# progtypec2.net
KiCad netlist of a schematic drawn in EAGLE
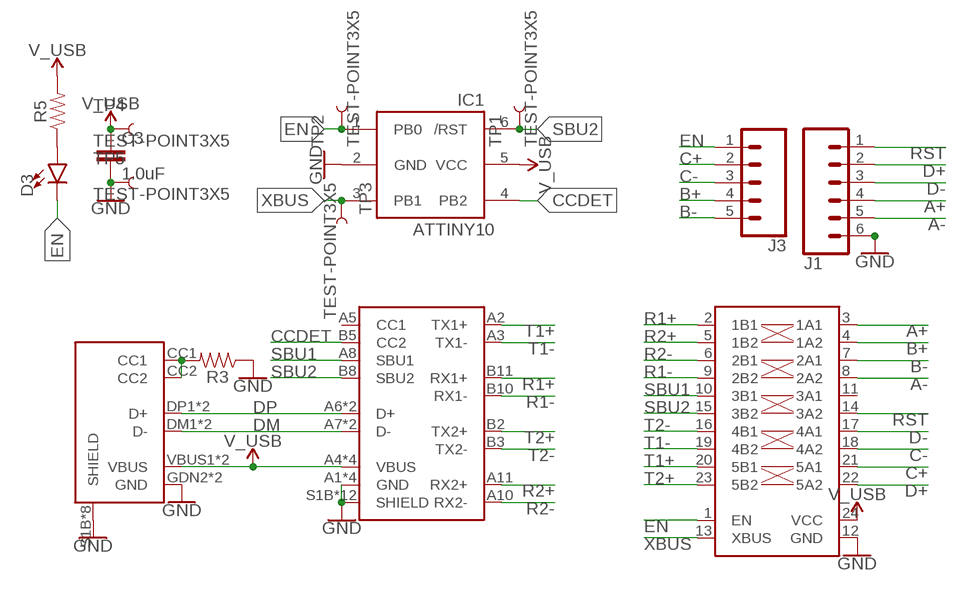
[diagram p0: schematic, sheet 1]

(export (version "E")
  (design (tool "Eeschema 10.0.6"))
  (components
    (comp (ref "C3")
      (value "1.0uF")
      (footprint "eagle-import:0603")
      (libsource (lib "eagle-import") (part "1.0UF-0603-16V-10%"))
    )
    (comp (ref "D3")
      (value "LED0603")
      (footprint "eagle-import:LED-0603")
      (libsource (lib "eagle-import") (part "LED0603"))
    )
    (comp (ref "IC1")
      (value "ATTINY10")
      (footprint "eagle-import:SOT23-6")
      (libsource (lib "eagle-import") (part "ATTINY10"))
    )
    (comp (ref "J1")
      (value "CONN_06NO_SILK_FEMALE_PTH")
      (footprint "eagle-import:1X06_NO_SILK")
      (libsource (lib "eagle-import") (part "CONN_06NO_SILK_FEMALE_PTH"))
    )
    (comp (ref "J3")
      (value "CONN_05NO_SILK")
      (footprint "eagle-import:1X05_NO_SILK")
      (libsource (lib "eagle-import") (part "CONN_05NO_SILK"))
    )
    (comp (ref "R3")
      (value "RESISTOR0603")
      (footprint "eagle-import:0603")
      (libsource (lib "eagle-import") (part "RESISTOR0603"))
    )
    (comp (ref "R5")
      (value "RESISTOR0603")
      (footprint "eagle-import:0603")
      (libsource (lib "eagle-import") (part "RESISTOR0603"))
    )
    (comp (ref "TP1")
      (value "TEST-POINT3X5")
      (footprint "eagle-import:PAD.03X.05")
      (libsource (lib "eagle-import") (part "TEST-POINT3X5"))
    )
    (comp (ref "TP2")
      (value "TEST-POINT3X5")
      (footprint "eagle-import:PAD.03X.05")
      (libsource (lib "eagle-import") (part "TEST-POINT3X5"))
    )
    (comp (ref "TP3")
      (value "TEST-POINT3X5")
      (footprint "eagle-import:PAD.03X.05")
      (libsource (lib "eagle-import") (part "TEST-POINT3X5"))
    )
    (comp (ref "TP4")
      (value "TEST-POINT3X5")
      (footprint "eagle-import:PAD.03X.05")
      (libsource (lib "eagle-import") (part "TEST-POINT3X5"))
    )
    (comp (ref "TP5")
      (value "TEST-POINT3X5")
      (footprint "eagle-import:PAD.03X.05")
      (libsource (lib "eagle-import") (part "TEST-POINT3X5"))
    )
    (comp (ref "U$1")
      (value "USB-C-HORZ-F")
      (footprint "eagle-import:USB-C_24PIN_HORZ-F-UNTESTED")
      (libsource (lib "eagle-import") (part "USB-C-HORZ-F"))
    )
    (comp (ref "U$2")
      (value "USB-C_USB2ONLY-HORZ-F_12P")
      (footprint "eagle-import:USB-C_12PIN_HORZ-F")
      (libsource (lib "eagle-import") (part "USB-C_USB2ONLY-HORZ-F_12P"))
    )
    (comp (ref "U$3")
      (value "SN74CBT3383C")
      (footprint "eagle-import:TSSOP24")
      (libsource (lib "eagle-import") (part "SN74CBT3383C"))
    )
  )
  (nets
    (net (code "1") (name "A+") (class "Default")
      (node (ref "J1") (pin "4") (pinfunction "4_4") (pintype "passive"))
      (node (ref "U$3") (pin "3") (pinfunction "1A1_3") (pintype "bidirectional"))
    )
    (net (code "2") (name "A-") (class "Default")
      (node (ref "J1") (pin "5") (pinfunction "5_5") (pintype "passive"))
      (node (ref "U$3") (pin "8") (pinfunction "2A2_8") (pintype "bidirectional"))
    )
    (net (code "3") (name "B+") (class "Default")
      (node (ref "J3") (pin "4") (pinfunction "4_4") (pintype "passive"))
      (node (ref "U$3") (pin "4") (pinfunction "1A2_4") (pintype "bidirectional"))
    )
    (net (code "4") (name "B-") (class "Default")
      (node (ref "J3") (pin "5") (pinfunction "5_5") (pintype "passive"))
      (node (ref "U$3") (pin "7") (pinfunction "2A1_7") (pintype "bidirectional"))
    )
    (net (code "5") (name "C+") (class "Default")
      (node (ref "J3") (pin "2") (pinfunction "2_2") (pintype "passive"))
      (node (ref "U$3") (pin "21") (pinfunction "5A1_21") (pintype "bidirectional"))
    )
    (net (code "6") (name "C-") (class "Default")
      (node (ref "J3") (pin "3") (pinfunction "3_3") (pintype "passive"))
      (node (ref "U$3") (pin "18") (pinfunction "4A2_18") (pintype "bidirectional"))
    )
    (net (code "7") (name "CCDET") (class "Default")
      (node (ref "IC1") (pin "4") (pinfunction "PB2_4") (pintype "bidirectional"))
      (node (ref "U$1") (pin "B5") (pinfunction "CC2_B5") (pintype "bidirectional"))
    )
    (net (code "8") (name "D+") (class "Default")
      (node (ref "J1") (pin "2") (pinfunction "2_2") (pintype "passive"))
      (node (ref "U$3") (pin "22") (pinfunction "5A2_22") (pintype "bidirectional"))
    )
    (net (code "9") (name "D-") (class "Default")
      (node (ref "J1") (pin "3") (pinfunction "3_3") (pintype "passive"))
      (node (ref "U$3") (pin "17") (pinfunction "4A1_17") (pintype "bidirectional"))
    )
    (net (code "10") (name "DM") (class "Default")
      (node (ref "U$1") (pin "A7") (pinfunction "D-_A7") (pintype "bidirectional"))
      (node (ref "U$1") (pin "B7") (pinfunction "D-_B7") (pintype "bidirectional"))
      (node (ref "U$2") (pin "DM1") (pinfunction "D-_DM1") (pintype "bidirectional"))
      (node (ref "U$2") (pin "DM2") (pinfunction "D-_DM2") (pintype "bidirectional"))
    )
    (net (code "11") (name "DP") (class "Default")
      (node (ref "U$1") (pin "A6") (pinfunction "D+_A6") (pintype "bidirectional"))
      (node (ref "U$1") (pin "B6") (pinfunction "D+_B6") (pintype "bidirectional"))
      (node (ref "U$2") (pin "DP1") (pinfunction "D+_DP1") (pintype "bidirectional"))
      (node (ref "U$2") (pin "DP2") (pinfunction "D+_DP2") (pintype "bidirectional"))
    )
    (net (code "12") (name "EN") (class "Default")
      (node (ref "D3") (pin "C") (pinfunction "C_C") (pintype "passive"))
      (node (ref "IC1") (pin "1") (pinfunction "PB0_1") (pintype "bidirectional"))
      (node (ref "J3") (pin "1") (pinfunction "1_1") (pintype "passive"))
      (node (ref "TP2") (pin "P$1") (pinfunction "1_P$1") (pintype "bidirectional"))
      (node (ref "U$3") (pin "1") (pinfunction "EN_1") (pintype "bidirectional"))
    )
    (net (code "13") (name "GND") (class "Default")
      (node (ref "C3") (pin "2") (pinfunction "2_2") (pintype "passive"))
      (node (ref "IC1") (pin "2") (pinfunction "GND_2") (pintype "power_in"))
      (node (ref "J1") (pin "6") (pinfunction "6_6") (pintype "passive"))
      (node (ref "R3") (pin "1") (pinfunction "1_1") (pintype "passive"))
      (node (ref "TP5") (pin "P$1") (pinfunction "1_P$1") (pintype "bidirectional"))
      (node (ref "U$1") (pin "A1") (pinfunction "GND_A1") (pintype "bidirectional"))
      (node (ref "U$1") (pin "A12") (pinfunction "GND_A12") (pintype "bidirectional"))
      (node (ref "U$1") (pin "B1") (pinfunction "GND_B1") (pintype "bidirectional"))
      (node (ref "U$1") (pin "B12") (pinfunction "GND_B12") (pintype "bidirectional"))
      (node (ref "U$1") (pin "S1B") (pinfunction "SHIELD_S1B") (pintype "bidirectional"))
      (node (ref "U$1") (pin "S1T") (pinfunction "SHIELD_S1T") (pintype "bidirectional"))
      (node (ref "U$1") (pin "S2B") (pinfunction "SHIELD_S2B") (pintype "bidirectional"))
      (node (ref "U$1") (pin "S2T") (pinfunction "SHIELD_S2T") (pintype "bidirectional"))
      (node (ref "U$1") (pin "S3B") (pinfunction "SHIELD_S3B") (pintype "bidirectional"))
      (node (ref "U$1") (pin "S3T") (pinfunction "SHIELD_S3T") (pintype "bidirectional"))
      (node (ref "U$1") (pin "S4B") (pinfunction "SHIELD_S4B") (pintype "bidirectional"))
      (node (ref "U$1") (pin "S4T") (pinfunction "SHIELD_S4T") (pintype "bidirectional"))
      (node (ref "U$1") (pin "S5B") (pinfunction "SHIELD_S5B") (pintype "bidirectional"))
      (node (ref "U$1") (pin "S5T") (pinfunction "SHIELD_S5T") (pintype "bidirectional"))
      (node (ref "U$1") (pin "S6B") (pinfunction "SHIELD_S6B") (pintype "bidirectional"))
      (node (ref "U$1") (pin "S6T") (pinfunction "SHIELD_S6T") (pintype "bidirectional"))
      (node (ref "U$2") (pin "GDN2") (pinfunction "GND_GDN2") (pintype "bidirectional"))
      (node (ref "U$2") (pin "GND1") (pinfunction "GND_GND1") (pintype "bidirectional"))
      (node (ref "U$2") (pin "S1B") (pinfunction "SHIELD_S1B") (pintype "bidirectional"))
      (node (ref "U$2") (pin "S1T") (pinfunction "SHIELD_S1T") (pintype "bidirectional"))
      (node (ref "U$2") (pin "S2B") (pinfunction "SHIELD_S2B") (pintype "bidirectional"))
      (node (ref "U$2") (pin "S2T") (pinfunction "SHIELD_S2T") (pintype "bidirectional"))
      (node (ref "U$2") (pin "S3B") (pinfunction "SHIELD_S3B") (pintype "bidirectional"))
      (node (ref "U$2") (pin "S3T") (pinfunction "SHIELD_S3T") (pintype "bidirectional"))
      (node (ref "U$2") (pin "S4B") (pinfunction "SHIELD_S4B") (pintype "bidirectional"))
      (node (ref "U$2") (pin "S4T") (pinfunction "SHIELD_S4T") (pintype "bidirectional"))
      (node (ref "U$3") (pin "12") (pinfunction "GND_12") (pintype "bidirectional"))
    )
    (net (code "14") (name "Net-(D3-PadA)") (class "Default")
      (node (ref "D3") (pin "A") (pinfunction "A_A") (pintype "passive"))
      (node (ref "R5") (pin "1") (pinfunction "1_1") (pintype "passive"))
    )
    (net (code "15") (name "Net-(R3-Pad2)") (class "Default")
      (node (ref "R3") (pin "2") (pinfunction "2_2") (pintype "passive"))
      (node (ref "U$2") (pin "CC1") (pinfunction "CC1_CC1") (pintype "bidirectional"))
      (node (ref "U$2") (pin "CC2") (pinfunction "CC2_CC2") (pintype "bidirectional"))
    )
    (net (code "16") (name "R1+") (class "Default")
      (node (ref "U$1") (pin "B11") (pinfunction "RX1+_B11") (pintype "bidirectional"))
      (node (ref "U$3") (pin "2") (pinfunction "1B1_2") (pintype "bidirectional"))
    )
    (net (code "17") (name "R1-") (class "Default")
      (node (ref "U$1") (pin "B10") (pinfunction "RX1-_B10") (pintype "bidirectional"))
      (node (ref "U$3") (pin "9") (pinfunction "2B2_9") (pintype "bidirectional"))
    )
    (net (code "18") (name "R2+") (class "Default")
      (node (ref "U$1") (pin "A11") (pinfunction "RX2+_A11") (pintype "bidirectional"))
      (node (ref "U$3") (pin "5") (pinfunction "1B2_5") (pintype "bidirectional"))
    )
    (net (code "19") (name "R2-") (class "Default")
      (node (ref "U$1") (pin "A10") (pinfunction "RX2-_A10") (pintype "bidirectional"))
      (node (ref "U$3") (pin "6") (pinfunction "2B1_6") (pintype "bidirectional"))
    )
    (net (code "20") (name "RST") (class "Default")
      (node (ref "J1") (pin "1") (pinfunction "1_1") (pintype "passive"))
      (node (ref "U$3") (pin "14") (pinfunction "3A2_14") (pintype "bidirectional"))
    )
    (net (code "21") (name "SBU1") (class "Default")
      (node (ref "U$1") (pin "A8") (pinfunction "SBU1_A8") (pintype "bidirectional"))
      (node (ref "U$3") (pin "10") (pinfunction "3B1_10") (pintype "bidirectional"))
    )
    (net (code "22") (name "SBU2") (class "Default")
      (node (ref "IC1") (pin "6") (pinfunction "/RST_6") (pintype "bidirectional"))
      (node (ref "TP1") (pin "P$1") (pinfunction "1_P$1") (pintype "bidirectional"))
      (node (ref "U$1") (pin "B8") (pinfunction "SBU2_B8") (pintype "bidirectional"))
      (node (ref "U$3") (pin "15") (pinfunction "3B2_15") (pintype "bidirectional"))
    )
    (net (code "23") (name "T1+") (class "Default")
      (node (ref "U$1") (pin "A2") (pinfunction "TX1+_A2") (pintype "bidirectional"))
      (node (ref "U$3") (pin "20") (pinfunction "5B1_20") (pintype "bidirectional"))
    )
    (net (code "24") (name "T1-") (class "Default")
      (node (ref "U$1") (pin "A3") (pinfunction "TX1-_A3") (pintype "bidirectional"))
      (node (ref "U$3") (pin "19") (pinfunction "4B2_19") (pintype "bidirectional"))
    )
    (net (code "25") (name "T2+") (class "Default")
      (node (ref "U$1") (pin "B2") (pinfunction "TX2+_B2") (pintype "bidirectional"))
      (node (ref "U$3") (pin "23") (pinfunction "5B2_23") (pintype "bidirectional"))
    )
    (net (code "26") (name "T2-") (class "Default")
      (node (ref "U$1") (pin "B3") (pinfunction "TX2-_B3") (pintype "bidirectional"))
      (node (ref "U$3") (pin "16") (pinfunction "4B1_16") (pintype "bidirectional"))
    )
    (net (code "27") (name "V_USB") (class "Default")
      (node (ref "C3") (pin "1") (pinfunction "1_1") (pintype "passive"))
      (node (ref "IC1") (pin "5") (pinfunction "VCC_5") (pintype "power_in"))
      (node (ref "R5") (pin "2") (pinfunction "2_2") (pintype "passive"))
      (node (ref "TP4") (pin "P$1") (pinfunction "1_P$1") (pintype "bidirectional"))
      (node (ref "U$1") (pin "A4") (pinfunction "VBUS_A4") (pintype "bidirectional"))
      (node (ref "U$1") (pin "A9") (pinfunction "VBUS_A9") (pintype "bidirectional"))
      (node (ref "U$1") (pin "B4") (pinfunction "VBUS_B4") (pintype "bidirectional"))
      (node (ref "U$1") (pin "B9") (pinfunction "VBUS_B9") (pintype "bidirectional"))
      (node (ref "U$2") (pin "VBUS1") (pinfunction "VBUS_VBUS1") (pintype "bidirectional"))
      (node (ref "U$2") (pin "VBUS2") (pinfunction "VBUS_VBUS2") (pintype "bidirectional"))
      (node (ref "U$3") (pin "24") (pinfunction "VCC_24") (pintype "bidirectional"))
    )
    (net (code "28") (name "XBUS") (class "Default")
      (node (ref "IC1") (pin "3") (pinfunction "PB1_3") (pintype "bidirectional"))
      (node (ref "TP3") (pin "P$1") (pinfunction "1_P$1") (pintype "bidirectional"))
      (node (ref "U$3") (pin "13") (pinfunction "XBUS_13") (pintype "bidirectional"))
    )
    (net (code "29") (name "unconnected-(U$1-CC1-PadA5)") (class "Default")
      (node (ref "U$1") (pin "A5") (pinfunction "CC1_A5") (pintype "bidirectional"))
    )
    (net (code "30") (name "unconnected-(U$3-3A1-Pad11)") (class "Default")
      (node (ref "U$3") (pin "11") (pinfunction "3A1_11") (pintype "bidirectional"))
    )
  )
)
